# Multi_STM32_V0_1.net
KiCad netlist of a schematic drawn in EAGLE
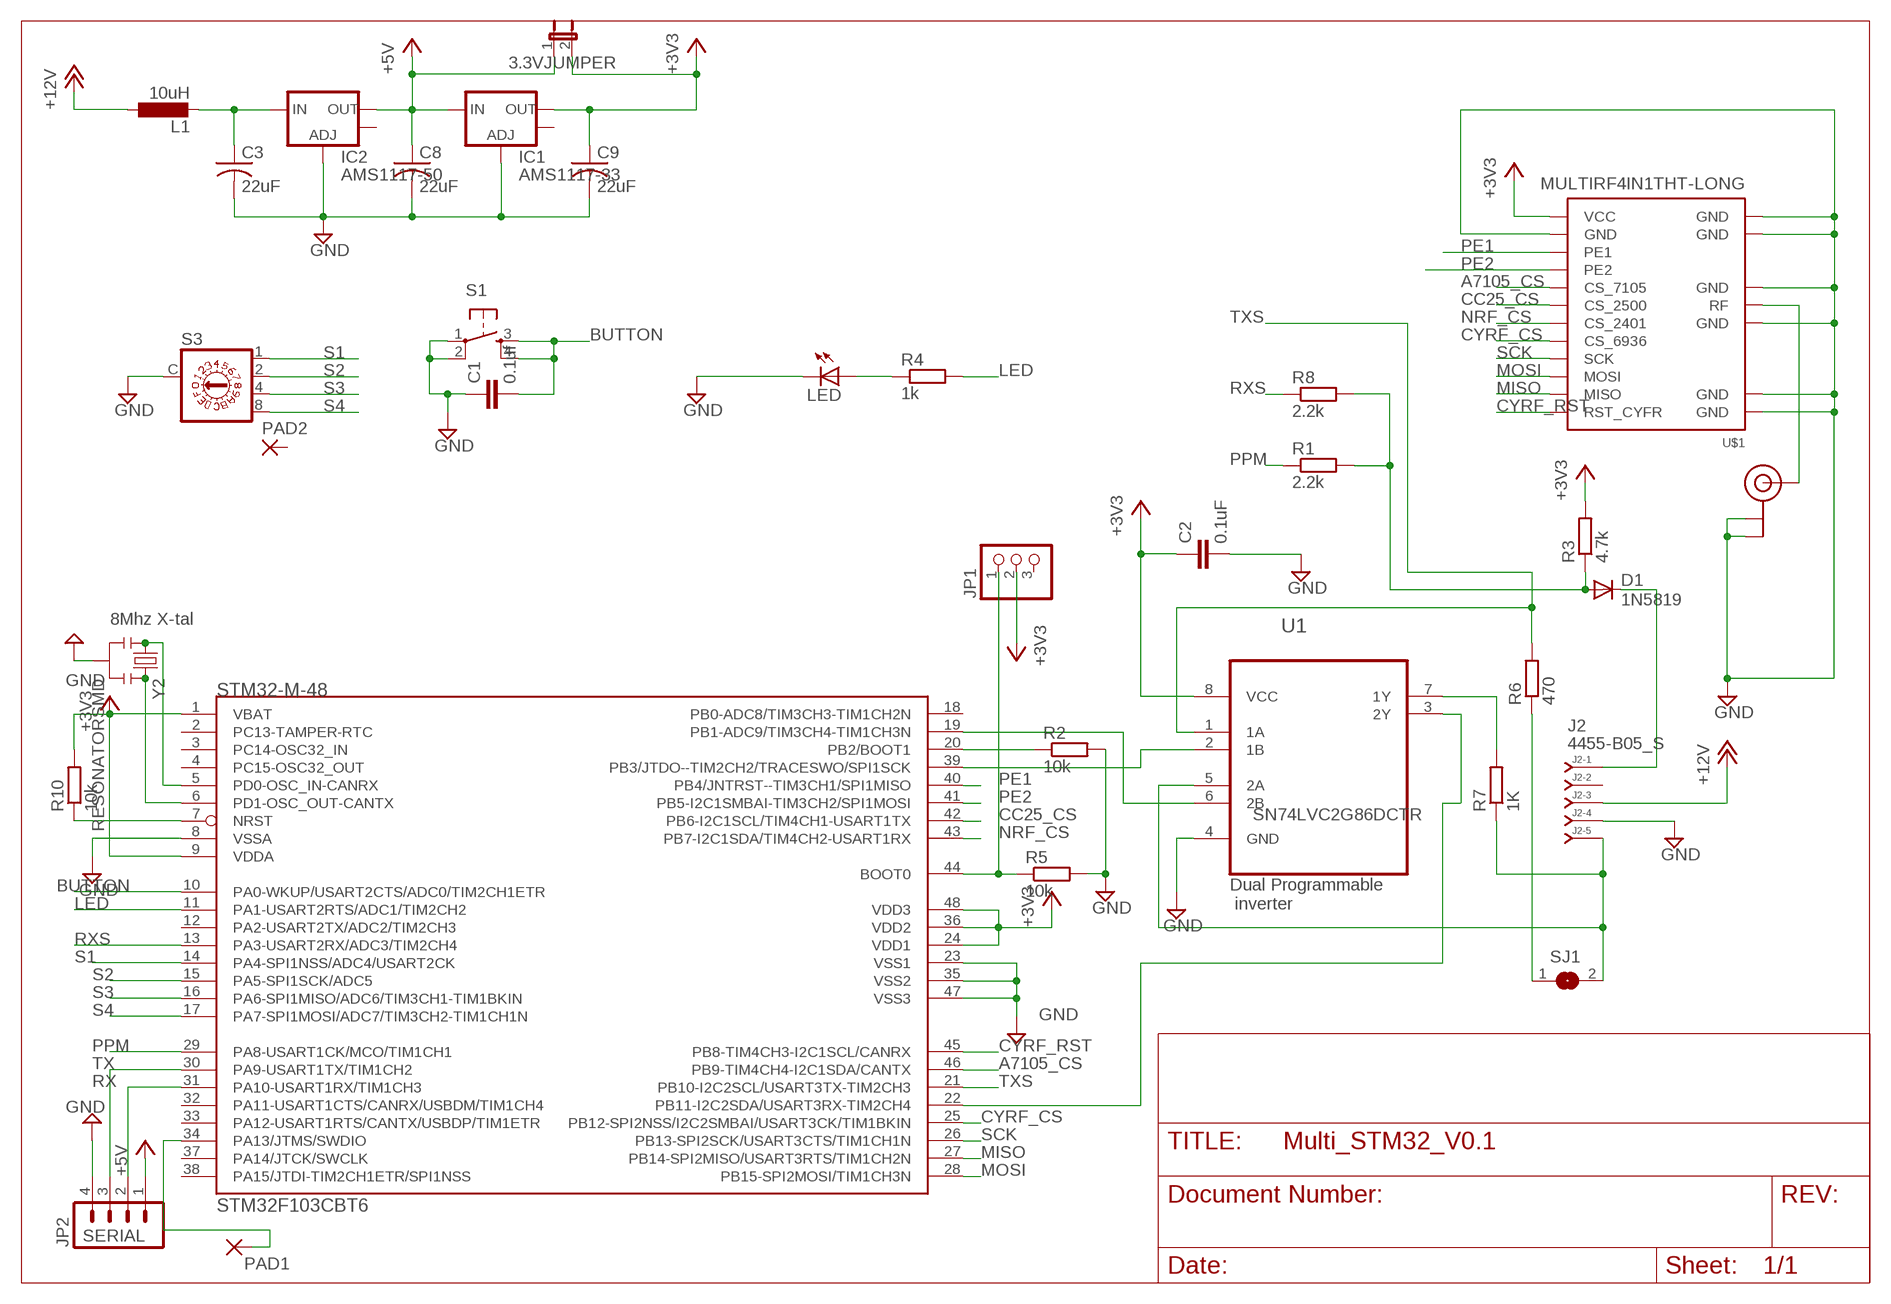
[diagram p0: schematic, sheet 1]

(export (version "E")
  (design (tool "Eeschema 10.0.6"))
  (components
    (comp (ref "3.3VJUMPER")
      (value "JUMPER-2PTH")
      (footprint "eagle-import:1X02")
      (libsource (lib "eagle-import") (part "JUMPER-2PTH"))
    )
    (comp (ref "C1")
      (value "0.1uf")
      (footprint "eagle-import:C0805")
      (libsource (lib "eagle-import") (part "C-EUC0805"))
    )
    (comp (ref "C2")
      (value "0.1uF")
      (footprint "eagle-import:C0805")
      (libsource (lib "eagle-import") (part "C-EUC0805"))
    )
    (comp (ref "C3")
      (value "22uF")
      (footprint "eagle-import:C1206")
      (libsource (lib "eagle-import") (part "C-USC1206"))
    )
    (comp (ref "C8")
      (value "22uF")
      (footprint "eagle-import:C1206")
      (libsource (lib "eagle-import") (part "C-USC1206"))
    )
    (comp (ref "C9")
      (value "22uF")
      (footprint "eagle-import:C1206")
      (libsource (lib "eagle-import") (part "C-USC1206"))
    )
    (comp (ref "D1")
      (value "1N5819")
      (footprint "eagle-import:SMA-DIODE_ALT")
      (libsource (lib "eagle-import") (part "DIODESMA-ALT"))
    )
    (comp (ref "IC1")
      (value "AMS1117-33")
      (footprint "eagle-import:SOT223")
      (libsource (lib "eagle-import") (part "V_REG_LM1117SOT223"))
    )
    (comp (ref "IC2")
      (value "AMS1117-50")
      (footprint "eagle-import:SOT223")
      (libsource (lib "eagle-import") (part "V_REG_LM1117SOT223"))
    )
    (comp (ref "J2")
      (value "4455-B05_S")
      (footprint "eagle-import:4455-B05")
      (libsource (lib "eagle-import") (part "4455-B05_S"))
    )
    (comp (ref "JP1")
      (value "PINHD-1X3")
      (footprint "eagle-import:1X03")
      (libsource (lib "eagle-import") (part "PINHD-1X3"))
    )
    (comp (ref "JP2")
      (value "SERIAL")
      (footprint "eagle-import:1X04")
      (libsource (lib "eagle-import") (part "M04PTH"))
    )
    (comp (ref "L1")
      (value "10uH")
      (footprint "eagle-import:L1812")
      (libsource (lib "eagle-import") (part "L-EUL1812"))
    )
    (comp (ref "LED")
      (value "LED3MM")
      (footprint "eagle-import:LED3MM")
      (libsource (lib "eagle-import") (part "LED3MM"))
    )
    (comp (ref "PAD1")
      (value "SMD2")
      (footprint "eagle-import:SMD1,27-2,54")
      (libsource (lib "eagle-import") (part "SMD2"))
    )
    (comp (ref "PAD2")
      (value "1,6/0,8")
      (footprint "eagle-import:1,6_0,8")
      (libsource (lib "eagle-import") (part "1,6/0,8"))
    )
    (comp (ref "R1")
      (value "2.2k")
      (footprint "eagle-import:R0805")
      (libsource (lib "eagle-import") (part "R-EU_R0805"))
    )
    (comp (ref "R2")
      (value "10k")
      (footprint "eagle-import:R0805")
      (libsource (lib "eagle-import") (part "R-EU_R0805"))
    )
    (comp (ref "R3")
      (value "4.7k")
      (footprint "eagle-import:R0805")
      (libsource (lib "eagle-import") (part "R-EU_R0805"))
    )
    (comp (ref "R4")
      (value "1k")
      (footprint "eagle-import:R0805")
      (libsource (lib "eagle-import") (part "R-EU_R0805"))
    )
    (comp (ref "R5")
      (value "10k")
      (footprint "eagle-import:R0805")
      (libsource (lib "eagle-import") (part "R-EU_R0805"))
    )
    (comp (ref "R6")
      (value "470")
      (footprint "eagle-import:R0805")
      (libsource (lib "eagle-import") (part "R-EU_R0805"))
    )
    (comp (ref "R7")
      (value "1K")
      (footprint "eagle-import:R0805")
      (libsource (lib "eagle-import") (part "R-EU_R0805"))
    )
    (comp (ref "R8")
      (value "2.2k")
      (footprint "eagle-import:R0805")
      (libsource (lib "eagle-import") (part "R-EU_R0805"))
    )
    (comp (ref "R10")
      (value "10k")
      (footprint "eagle-import:R0805")
      (libsource (lib "eagle-import") (part "R-EU_R0805"))
    )
    (comp (ref "S1")
      (value "TAC_SWITCHPTH")
      (footprint "eagle-import:TACTILE-PTH")
      (libsource (lib "eagle-import") (part "TAC_SWITCHPTH"))
    )
    (comp (ref "S3")
      (value "A1353HEX")
      (footprint "eagle-import:A1353HEX")
      (libsource (lib "eagle-import") (part "A1353HEX"))
    )
    (comp (ref "SJ1") (value "SJ") (footprint "eagle-import:SJ") (libsource (lib "eagle-import") (part "SJ")))
    (comp (ref "STM32F103CBT6")
      (value "STM32-M-48")
      (footprint "eagle-import:LQFP48")
      (libsource (lib "eagle-import") (part "STM32-M-48"))
    )
    (comp (ref "U$1")
      (value "MULTIRF4IN1THT-LONG")
      (footprint "eagle-import:MULTIRF4IN1-THT-LONG")
      (libsource (lib "eagle-import") (part "MULTIRF4IN1THT-LONG"))
    )
    (comp (ref "U$2")
      (value "U.FL")
      (footprint "eagle-import:U.FL")
      (libsource (lib "eagle-import") (part "U.FL"))
    )
    (comp (ref "U1")
      (value "SN74LVC2G00DCTR")
      (footprint "eagle-import:SOP65P400X130-8N")
      (libsource (lib "eagle-import") (part "SN74LVC2G00DCTR"))
    )
    (comp (ref "Y2")
      (value "RESONATORSMD")
      (footprint "eagle-import:RESONATOR-SMD")
      (libsource (lib "eagle-import") (part "RESONATORSMD"))
    )
  )
  (nets
    (net (code "1") (name "+3V3") (class "Default")
      (node (ref "3.3VJUMPER") (pin "2") (pinfunction "2_2") (pintype "passive"))
      (node (ref "C2") (pin "1") (pinfunction "1_1") (pintype "passive"))
      (node (ref "C9") (pin "1") (pinfunction "1_1") (pintype "passive"))
      (node (ref "IC1") (pin "2") (pinfunction "OUT_2") (pintype "output"))
      (node (ref "JP1") (pin "2") (pinfunction "2_2") (pintype "passive"))
      (node (ref "R10") (pin "2") (pinfunction "2_2") (pintype "passive"))
      (node (ref "R3") (pin "2") (pinfunction "2_2") (pintype "passive"))
      (node (ref "STM32F103CBT6") (pin "1") (pinfunction "VBAT_1") (pintype "power_in"))
      (node (ref "STM32F103CBT6") (pin "24") (pinfunction "VDD1_24") (pintype "power_in"))
      (node (ref "STM32F103CBT6") (pin "36") (pinfunction "VDD2_36") (pintype "power_in"))
      (node (ref "STM32F103CBT6") (pin "48") (pinfunction "VDD3_48") (pintype "power_in"))
      (node (ref "STM32F103CBT6") (pin "9") (pinfunction "VDDA_9") (pintype "power_in"))
      (node (ref "U$1") (pin "VCC") (pinfunction "VCC_VCC") (pintype "power_in"))
      (node (ref "U1") (pin "8") (pinfunction "VCC_8") (pintype "power_in"))
    )
    (net (code "2") (name "+5V") (class "Default")
      (node (ref "3.3VJUMPER") (pin "1") (pinfunction "1_1") (pintype "passive"))
      (node (ref "C8") (pin "1") (pinfunction "1_1") (pintype "passive"))
      (node (ref "IC1") (pin "3") (pinfunction "IN_3") (pintype "input"))
      (node (ref "IC2") (pin "2") (pinfunction "OUT_2") (pintype "output"))
      (node (ref "JP2") (pin "1") (pinfunction "1_1") (pintype "passive"))
    )
    (net (code "3") (name "+12V") (class "Default")
      (node (ref "J2") (pin "3") (pinfunction "J_3") (pintype "passive"))
      (node (ref "L1") (pin "1") (pinfunction "1_1") (pintype "passive"))
    )
    (net (code "4") (name "/A7105_CS") (class "Default")
      (node (ref "STM32F103CBT6") (pin "46") (pinfunction "PB9-TIM4CH4-I2C1SDA/CANTX_46") (pintype "bidirectional"))
      (node (ref "U$1") (pin "CS_7105") (pinfunction "CS_7105_CS_7105") (pintype "bidirectional"))
    )
    (net (code "5") (name "/BUTTON") (class "Default")
      (node (ref "C1") (pin "2") (pinfunction "2_2") (pintype "passive"))
      (node (ref "S1") (pin "3") (pinfunction "3_3") (pintype "passive"))
      (node (ref "S1") (pin "4") (pinfunction "4_4") (pintype "passive"))
      (node (ref "STM32F103CBT6") (pin "10") (pinfunction "PA0-WKUP/USART2CTS/ADC0/TIM2CH1ETR_10") (pintype "bidirectional"))
    )
    (net (code "6") (name "/CC25_CS") (class "Default")
      (node (ref "STM32F103CBT6") (pin "42") (pinfunction "PB6-I2C1SCL/TIM4CH1-USART1TX_42") (pintype "bidirectional"))
      (node (ref "U$1") (pin "CS_2500") (pinfunction "CS_2500_CS_2500") (pintype "bidirectional"))
    )
    (net (code "7") (name "/CYRF_CS") (class "Default")
      (node (ref "STM32F103CBT6") (pin "25") (pinfunction "PB12-SPI2NSS/I2C2SMBAI/USART3CK/TIM1BKIN_25") (pintype "bidirectional"))
      (node (ref "U$1") (pin "CS_6936") (pinfunction "CS_6936_CS_6936") (pintype "bidirectional"))
    )
    (net (code "8") (name "/CYRF_RST") (class "Default")
      (node (ref "STM32F103CBT6") (pin "45") (pinfunction "PB8-TIM4CH3-I2C1SCL/CANRX_45") (pintype "bidirectional"))
      (node (ref "U$1") (pin "RST_CYFR") (pinfunction "RST_CYFR_RST_CYFR") (pintype "bidirectional"))
    )
    (net (code "9") (name "/LED") (class "Default")
      (node (ref "R4") (pin "2") (pinfunction "2_2") (pintype "passive"))
      (node (ref "STM32F103CBT6") (pin "11") (pinfunction "PA1-USART2RTS/ADC1/TIM2CH2_11") (pintype "bidirectional"))
    )
    (net (code "10") (name "/MISO") (class "Default")
      (node (ref "STM32F103CBT6") (pin "27") (pinfunction "PB14-SPI2MISO/USART3RTS/TIM1CH2N_27") (pintype "bidirectional"))
      (node (ref "U$1") (pin "MISO") (pinfunction "MISO_MISO") (pintype "bidirectional"))
    )
    (net (code "11") (name "/MOSI") (class "Default")
      (node (ref "STM32F103CBT6") (pin "28") (pinfunction "PB15-SPI2MOSI/TIM1CH3N_28") (pintype "bidirectional"))
      (node (ref "U$1") (pin "MOSI") (pinfunction "MOSI_MOSI") (pintype "bidirectional"))
    )
    (net (code "12") (name "/NRF_CS") (class "Default")
      (node (ref "STM32F103CBT6") (pin "43") (pinfunction "PB7-I2C1SDA/TIM4CH2-USART1RX_43") (pintype "bidirectional"))
      (node (ref "U$1") (pin "CS_2401") (pinfunction "CS_2401_CS_2401") (pintype "bidirectional"))
    )
    (net (code "13") (name "/PE1") (class "Default")
      (node (ref "STM32F103CBT6") (pin "40") (pinfunction "PB4/JNTRST--TIM3CH1/SPI1MISO_40") (pintype "bidirectional"))
      (node (ref "U$1") (pin "PE1") (pinfunction "PE1_PE1") (pintype "bidirectional"))
    )
    (net (code "14") (name "/PE2") (class "Default")
      (node (ref "STM32F103CBT6") (pin "41") (pinfunction "PB5-I2C1SMBAI-TIM3CH2/SPI1MOSI_41") (pintype "bidirectional"))
      (node (ref "U$1") (pin "PE2") (pinfunction "PE2_PE2") (pintype "bidirectional"))
    )
    (net (code "15") (name "/PPM") (class "Default")
      (node (ref "R1") (pin "1") (pinfunction "1_1") (pintype "passive"))
      (node (ref "STM32F103CBT6") (pin "29") (pinfunction "PA8-USART1CK/MCO/TIM1CH1_29") (pintype "bidirectional"))
    )
    (net (code "16") (name "/RX") (class "Default")
      (node (ref "JP2") (pin "2") (pinfunction "2_2") (pintype "passive"))
      (node (ref "STM32F103CBT6") (pin "31") (pinfunction "PA10-USART1RX/TIM1CH3_31") (pintype "bidirectional"))
    )
    (net (code "17") (name "/RXS") (class "Default")
      (node (ref "R8") (pin "1") (pinfunction "1_1") (pintype "passive"))
      (node (ref "STM32F103CBT6") (pin "13") (pinfunction "PA3-USART2RX/ADC3/TIM2CH4_13") (pintype "bidirectional"))
    )
    (net (code "18") (name "/S1") (class "Default")
      (node (ref "S3") (pin "1") (pinfunction "1_1") (pintype "passive"))
      (node (ref "STM32F103CBT6") (pin "14") (pinfunction "PA4-SPI1NSS/ADC4/USART2CK_14") (pintype "bidirectional"))
    )
    (net (code "19") (name "/S2") (class "Default")
      (node (ref "S3") (pin "2") (pinfunction "2_2") (pintype "passive"))
      (node (ref "STM32F103CBT6") (pin "15") (pinfunction "PA5-SPI1SCK/ADC5_15") (pintype "bidirectional"))
    )
    (net (code "20") (name "/S3") (class "Default")
      (node (ref "S3") (pin "4") (pinfunction "4_4") (pintype "passive"))
      (node (ref "STM32F103CBT6") (pin "16") (pinfunction "PA6-SPI1MISO/ADC6/TIM3CH1-TIM1BKIN_16") (pintype "bidirectional"))
    )
    (net (code "21") (name "/S4") (class "Default")
      (node (ref "S3") (pin "8") (pinfunction "8_8") (pintype "passive"))
      (node (ref "STM32F103CBT6") (pin "17") (pinfunction "PA7-SPI1MOSI/ADC7/TIM3CH2-TIM1CH1N_17") (pintype "bidirectional"))
    )
    (net (code "22") (name "/SCK") (class "Default")
      (node (ref "STM32F103CBT6") (pin "26") (pinfunction "PB13-SPI2SCK/USART3CTS/TIM1CH1N_26") (pintype "bidirectional"))
      (node (ref "U$1") (pin "SCK") (pinfunction "SCK_SCK") (pintype "bidirectional"))
    )
    (net (code "23") (name "/TX") (class "Default")
      (node (ref "JP2") (pin "3") (pinfunction "3_3") (pintype "passive"))
      (node (ref "STM32F103CBT6") (pin "30") (pinfunction "PA9-USART1TX/TIM1CH2_30") (pintype "bidirectional"))
    )
    (net (code "24") (name "/TXS") (class "Default")
      (node (ref "R6") (pin "2") (pinfunction "2_2") (pintype "passive"))
      (node (ref "STM32F103CBT6") (pin "21") (pinfunction "PB10-I2C2SCL/USART3TX-TIM2CH3_21") (pintype "bidirectional"))
      (node (ref "U1") (pin "1") (pinfunction "1A_1") (pintype "input"))
    )
    (net (code "25") (name "GND") (class "Default")
      (node (ref "C1") (pin "1") (pinfunction "1_1") (pintype "passive"))
      (node (ref "C2") (pin "2") (pinfunction "2_2") (pintype "passive"))
      (node (ref "C3") (pin "2") (pinfunction "2_2") (pintype "passive"))
      (node (ref "C8") (pin "2") (pinfunction "2_2") (pintype "passive"))
      (node (ref "C9") (pin "2") (pinfunction "2_2") (pintype "passive"))
      (node (ref "IC1") (pin "1") (pinfunction "ADJ_1") (pintype "input"))
      (node (ref "IC2") (pin "1") (pinfunction "ADJ_1") (pintype "input"))
      (node (ref "J2") (pin "4") (pinfunction "J_4") (pintype "passive"))
      (node (ref "JP2") (pin "4") (pinfunction "4_4") (pintype "passive"))
      (node (ref "LED") (pin "K") (pinfunction "C_K") (pintype "passive"))
      (node (ref "R2") (pin "2") (pinfunction "2_2") (pintype "passive"))
      (node (ref "R5") (pin "2") (pinfunction "2_2") (pintype "passive"))
      (node (ref "S1") (pin "1") (pinfunction "1_1") (pintype "passive"))
      (node (ref "S1") (pin "2") (pinfunction "2_2") (pintype "passive"))
      (node (ref "S3") (pin "C") (pinfunction "C_C") (pintype "passive"))
      (node (ref "STM32F103CBT6") (pin "23") (pinfunction "VSS1_23") (pintype "power_in"))
      (node (ref "STM32F103CBT6") (pin "35") (pinfunction "VSS2_35") (pintype "power_in"))
      (node (ref "STM32F103CBT6") (pin "47") (pinfunction "VSS3_47") (pintype "power_in"))
      (node (ref "STM32F103CBT6") (pin "8") (pinfunction "VSSA_8") (pintype "power_in"))
      (node (ref "U$1") (pin "GND") (pinfunction "GND_GND") (pintype "power_in"))
      (node (ref "U$1") (pin "GND@1") (pinfunction "GND_GND@1") (pintype "power_in"))
      (node (ref "U$1") (pin "GND@2") (pinfunction "GND_GND@2") (pintype "power_in"))
      (node (ref "U$1") (pin "GND@3") (pinfunction "GND_GND@3") (pintype "power_in"))
      (node (ref "U$1") (pin "GND@4") (pinfunction "GND_GND@4") (pintype "power_in"))
      (node (ref "U$1") (pin "GND@5") (pinfunction "GND_GND@5") (pintype "power_in"))
      (node (ref "U$1") (pin "GND@6") (pinfunction "GND_GND@6") (pintype "power_in"))
      (node (ref "U$2") (pin "P$1") (pinfunction "GND_P$1") (pintype "bidirectional"))
      (node (ref "U$2") (pin "P$2") (pinfunction "GND_P$2") (pintype "bidirectional"))
      (node (ref "U1") (pin "4") (pinfunction "GND_4") (pintype "passive"))
      (node (ref "Y2") (pin "2") (pinfunction "2_2") (pintype "passive"))
    )
    (net (code "26") (name "Net-(D1-PadA)") (class "Default")
      (node (ref "D1") (pin "A") (pinfunction "A_A") (pintype "passive"))
      (node (ref "R1") (pin "2") (pinfunction "2_2") (pintype "passive"))
      (node (ref "R3") (pin "1") (pinfunction "1_1") (pintype "passive"))
      (node (ref "R8") (pin "2") (pinfunction "2_2") (pintype "passive"))
    )
    (net (code "27") (name "Net-(IC2-IN)") (class "Default")
      (node (ref "C3") (pin "1") (pinfunction "1_1") (pintype "passive"))
      (node (ref "IC2") (pin "3") (pinfunction "IN_3") (pintype "input"))
      (node (ref "L1") (pin "2") (pinfunction "2_2") (pintype "passive"))
    )
    (net (code "28") (name "Net-(J2A-J)") (class "Default")
      (node (ref "D1") (pin "C") (pinfunction "C_C") (pintype "passive"))
      (node (ref "J2") (pin "1") (pinfunction "J_1") (pintype "passive"))
    )
    (net (code "29") (name "Net-(J2E-J)") (class "Default")
      (node (ref "J2") (pin "5") (pinfunction "J_5") (pintype "passive"))
      (node (ref "R7") (pin "1") (pinfunction "1_1") (pintype "passive"))
      (node (ref "SJ1") (pin "2") (pinfunction "2_2") (pintype "passive"))
      (node (ref "U1") (pin "5") (pinfunction "2A_5") (pintype "input"))
    )
    (net (code "30") (name "Net-(LED-PadA)") (class "Default")
      (node (ref "LED") (pin "A") (pinfunction "A_A") (pintype "passive"))
      (node (ref "R4") (pin "1") (pinfunction "1_1") (pintype "passive"))
    )
    (net (code "31") (name "Net-(PAD1-P)") (class "Default")
      (node (ref "PAD1") (pin "1") (pinfunction "P_1") (pintype "passive"))
      (node (ref "STM32F103CBT6") (pin "34") (pinfunction "PA13/JTMS/SWDIO_34") (pintype "bidirectional"))
    )
    (net (code "32") (name "Net-(R6-Pad1)") (class "Default")
      (node (ref "R6") (pin "1") (pinfunction "1_1") (pintype "passive"))
      (node (ref "SJ1") (pin "1") (pinfunction "1_1") (pintype "passive"))
    )
    (net (code "33") (name "Net-(STM32F103CBT6-BOOT0)") (class "Default")
      (node (ref "JP1") (pin "1") (pinfunction "1_1") (pintype "passive"))
      (node (ref "R5") (pin "1") (pinfunction "1_1") (pintype "passive"))
      (node (ref "STM32F103CBT6") (pin "44") (pinfunction "BOOT0_44") (pintype "input"))
    )
    (net (code "34") (name "Net-(STM32F103CBT6-NRST)") (class "Default")
      (node (ref "R10") (pin "1") (pinfunction "1_1") (pintype "passive"))
      (node (ref "STM32F103CBT6") (pin "7") (pinfunction "NRST_7") (pintype "bidirectional"))
    )
    (net (code "35") (name "Net-(STM32F103CBT6-PB1-ADC9{slash}TIM3CH4-TIM1CH3N)") (class "Default")
      (node (ref "STM32F103CBT6") (pin "19") (pinfunction "PB1-ADC9/TIM3CH4-TIM1CH3N_19") (pintype "bidirectional"))
      (node (ref "U1") (pin "6") (pinfunction "2B_6") (pintype "input"))
    )
    (net (code "36") (name "Net-(STM32F103CBT6-PB2{slash}BOOT1)") (class "Default")
      (node (ref "R2") (pin "1") (pinfunction "1_1") (pintype "passive"))
      (node (ref "STM32F103CBT6") (pin "20") (pinfunction "PB2/BOOT1_20") (pintype "bidirectional"))
    )
    (net (code "37") (name "Net-(STM32F103CBT6-PB3{slash}JTDO--TIM2CH2{slash}TRACESWO{slash}SPI1SCK)") (class "Default")
      (node (ref "STM32F103CBT6") (pin "39") (pinfunction "PB3/JTDO--TIM2CH2/TRACESWO/SPI1SCK_39") (pintype "bidirectional"))
      (node (ref "U1") (pin "2") (pinfunction "1B_2") (pintype "input"))
    )
    (net (code "38") (name "Net-(STM32F103CBT6-PB11-I2C2SDA{slash}USART3RX-TIM2CH4)") (class "Default")
      (node (ref "STM32F103CBT6") (pin "22") (pinfunction "PB11-I2C2SDA/USART3RX-TIM2CH4_22") (pintype "bidirectional"))
      (node (ref "U1") (pin "3") (pinfunction "2Y_3") (pintype "output"))
    )
    (net (code "39") (name "Net-(STM32F103CBT6-PD0-OSC_IN-CANRX)") (class "Default")
      (node (ref "STM32F103CBT6") (pin "5") (pinfunction "PD0-OSC_IN-CANRX_5") (pintype "input"))
      (node (ref "Y2") (pin "1") (pinfunction "1_1") (pintype "passive"))
    )
    (net (code "40") (name "Net-(STM32F103CBT6-PD1-OSC_OUT-CANTX)") (class "Default")
      (node (ref "STM32F103CBT6") (pin "6") (pinfunction "PD1-OSC_OUT-CANTX_6") (pintype "output"))
      (node (ref "Y2") (pin "3") (pinfunction "3_3") (pintype "passive"))
    )
    (net (code "41") (name "Net-(U$2-SIGNAL)") (class "Default")
      (node (ref "U$1") (pin "RF") (pinfunction "RF_RF") (pintype "output"))
      (node (ref "U$2") (pin "P$3") (pinfunction "SIGNAL_P$3") (pintype "bidirectional"))
    )
    (net (code "42") (name "Net-(U1-1Y)") (class "Default")
      (node (ref "R7") (pin "2") (pinfunction "2_2") (pintype "passive"))
      (node (ref "U1") (pin "7") (pinfunction "1Y_7") (pintype "output"))
    )
    (net (code "43") (name "unconnected-(IC1-OUT-Pad4)") (class "Default")
      (node (ref "IC1") (pin "4") (pinfunction "OUT_4") (pintype "output"))
    )
    (net (code "44") (name "unconnected-(IC2-OUT-Pad4)") (class "Default")
      (node (ref "IC2") (pin "4") (pinfunction "OUT_4") (pintype "output"))
    )
    (net (code "45") (name "unconnected-(J2B-J-Pad2)") (class "Default")
      (node (ref "J2") (pin "2") (pinfunction "J_2") (pintype "passive"))
    )
    (net (code "46") (name "unconnected-(JP1-Pad3)") (class "Default")
      (node (ref "JP1") (pin "3") (pinfunction "3_3") (pintype "passive"))
    )
    (net (code "47") (name "unconnected-(PAD2-P-Pad1)") (class "Default")
      (node (ref "PAD2") (pin "1") (pinfunction "P_1") (pintype "passive"))
    )
    (net (code "48") (name "unconnected-(STM32F103CBT6-PA2-USART2TX{slash}ADC2{slash}TIM2CH3-Pad12)") (class "Default")
      (node (ref "STM32F103CBT6") (pin "12") (pinfunction "PA2-USART2TX/ADC2/TIM2CH3_12") (pintype "bidirectional"))
    )
    (net (code "49") (name "unconnected-(STM32F103CBT6-PA11-USART1CTS{slash}CANRX{slash}USBDM{slash}TIM1CH4-Pad32)") (class "Default")
      (node (ref "STM32F103CBT6") (pin "32") (pinfunction "PA11-USART1CTS/CANRX/USBDM/TIM1CH4_32") (pintype "bidirectional"))
    )
    (net (code "50") (name "unconnected-(STM32F103CBT6-PA12-USART1RTS{slash}CANTX{slash}USBDP{slash}TIM1ETR-Pad33)") (class "Default")
      (node (ref "STM32F103CBT6") (pin "33") (pinfunction "PA12-USART1RTS/CANTX/USBDP/TIM1ETR_33") (pintype "bidirectional"))
    )
    (net (code "51") (name "unconnected-(STM32F103CBT6-PA14{slash}JTCK{slash}SWCLK-Pad37)") (class "Default")
      (node (ref "STM32F103CBT6") (pin "37") (pinfunction "PA14/JTCK/SWCLK_37") (pintype "bidirectional"))
    )
    (net (code "52") (name "unconnected-(STM32F103CBT6-PA15{slash}JTDI-TIM2CH1ETR{slash}SPI1NSS-Pad38)") (class "Default")
      (node (ref "STM32F103CBT6") (pin "38") (pinfunction "PA15/JTDI-TIM2CH1ETR/SPI1NSS_38") (pintype "bidirectional"))
    )
    (net (code "53") (name "unconnected-(STM32F103CBT6-PB0-ADC8{slash}TIM3CH3-TIM1CH2N-Pad18)") (class "Default")
      (node (ref "STM32F103CBT6") (pin "18") (pinfunction "PB0-ADC8/TIM3CH3-TIM1CH2N_18") (pintype "bidirectional"))
    )
    (net (code "54") (name "unconnected-(STM32F103CBT6-PC13-TAMPER-RTC-Pad2)") (class "Default")
      (node (ref "STM32F103CBT6") (pin "2") (pinfunction "PC13-TAMPER-RTC_2") (pintype "bidirectional"))
    )
    (net (code "55") (name "unconnected-(STM32F103CBT6-PC14-OSC32_IN-Pad3)") (class "Default")
      (node (ref "STM32F103CBT6") (pin "3") (pinfunction "PC14-OSC32_IN_3") (pintype "bidirectional"))
    )
    (net (code "56") (name "unconnected-(STM32F103CBT6-PC15-OSC32_OUT-Pad4)") (class "Default")
      (node (ref "STM32F103CBT6") (pin "4") (pinfunction "PC15-OSC32_OUT_4") (pintype "bidirectional"))
    )
  )
)
